# temperature-sensor.net
KiCad netlist of a schematic drawn in Altium Designer
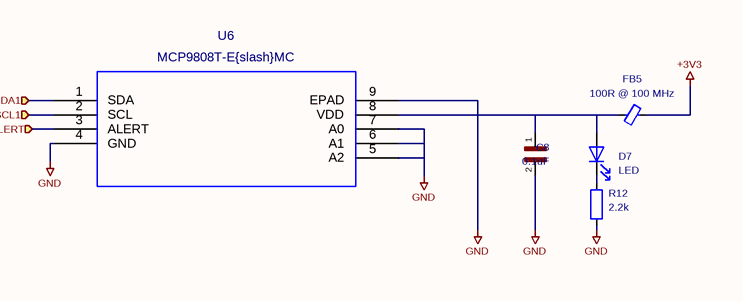
[diagram p0: temperature-sensor.SchDoc]

(export (version "E")
  (design (tool "Eeschema 10.0.6"))
  (components
    (comp (ref "C8") (value "0.1uF") (libsource (lib "Daughterboard_Symbols") (part "CL10B104KB8NNNL")))
    (comp (ref "D7") (value "LED") (libsource (lib "Device") (part "LED")))
    (comp (ref "FB5") (value "100R @ 100 MHz") (libsource (lib "Device") (part "FerriteBead_Small")))
    (comp (ref "R12") (value "2.2k") (libsource (lib "Device") (part "R")))
    (comp (ref "U6")
      (value "MCP9808T-E/MC")
      (libsource (lib "Daughterboard_Symbols") (part "MCP9808T-E{brace}slash}MC"))
    )
  )
  (nets
    (net (code "1") (name "+3V3") (class "Default")
      (node (ref "FB5") (pin "1") (pinfunction "1_1") (pintype "passive"))
    )
    (net (code "2") (name "/GPIO_TEMP_ALERT") (class "Default")
      (node (ref "U6") (pin "3") (pinfunction "ALERT_3") (pintype "passive"))
    )
    (net (code "3") (name "/I2C_SCL1") (class "Default")
      (node (ref "U6") (pin "2") (pinfunction "SCL_2") (pintype "passive"))
    )
    (net (code "4") (name "/I2C_SDA1") (class "Default")
      (node (ref "U6") (pin "1") (pinfunction "SDA_1") (pintype "passive"))
    )
    (net (code "5") (name "GND") (class "Default")
      (node (ref "C8") (pin "2") (pinfunction "2_2") (pintype "passive"))
      (node (ref "R12") (pin "2") (pinfunction "2_2") (pintype "passive"))
      (node (ref "U6") (pin "4") (pinfunction "GND_4") (pintype "passive"))
      (node (ref "U6") (pin "5") (pinfunction "A2_5") (pintype "passive"))
      (node (ref "U6") (pin "6") (pinfunction "A1_6") (pintype "passive"))
      (node (ref "U6") (pin "7") (pinfunction "A0_7") (pintype "passive"))
      (node (ref "U6") (pin "9") (pinfunction "EPAD_9") (pintype "passive"))
    )
    (net (code "6") (name "Net-(D7-A)") (class "Default")
      (node (ref "C8") (pin "1") (pinfunction "1_1") (pintype "passive"))
      (node (ref "D7") (pin "2") (pinfunction "A_2") (pintype "passive"))
      (node (ref "FB5") (pin "2") (pinfunction "2_2") (pintype "passive"))
      (node (ref "U6") (pin "8") (pinfunction "VDD_8") (pintype "passive"))
    )
    (net (code "7") (name "Net-(D7-K)") (class "Default")
      (node (ref "D7") (pin "1") (pinfunction "K_1") (pintype "passive"))
      (node (ref "R12") (pin "1") (pinfunction "1_1") (pintype "passive"))
    )
  )
)
